# Cyusb3014_-_2.net
KiCad netlist of a schematic drawn in Altium Designer
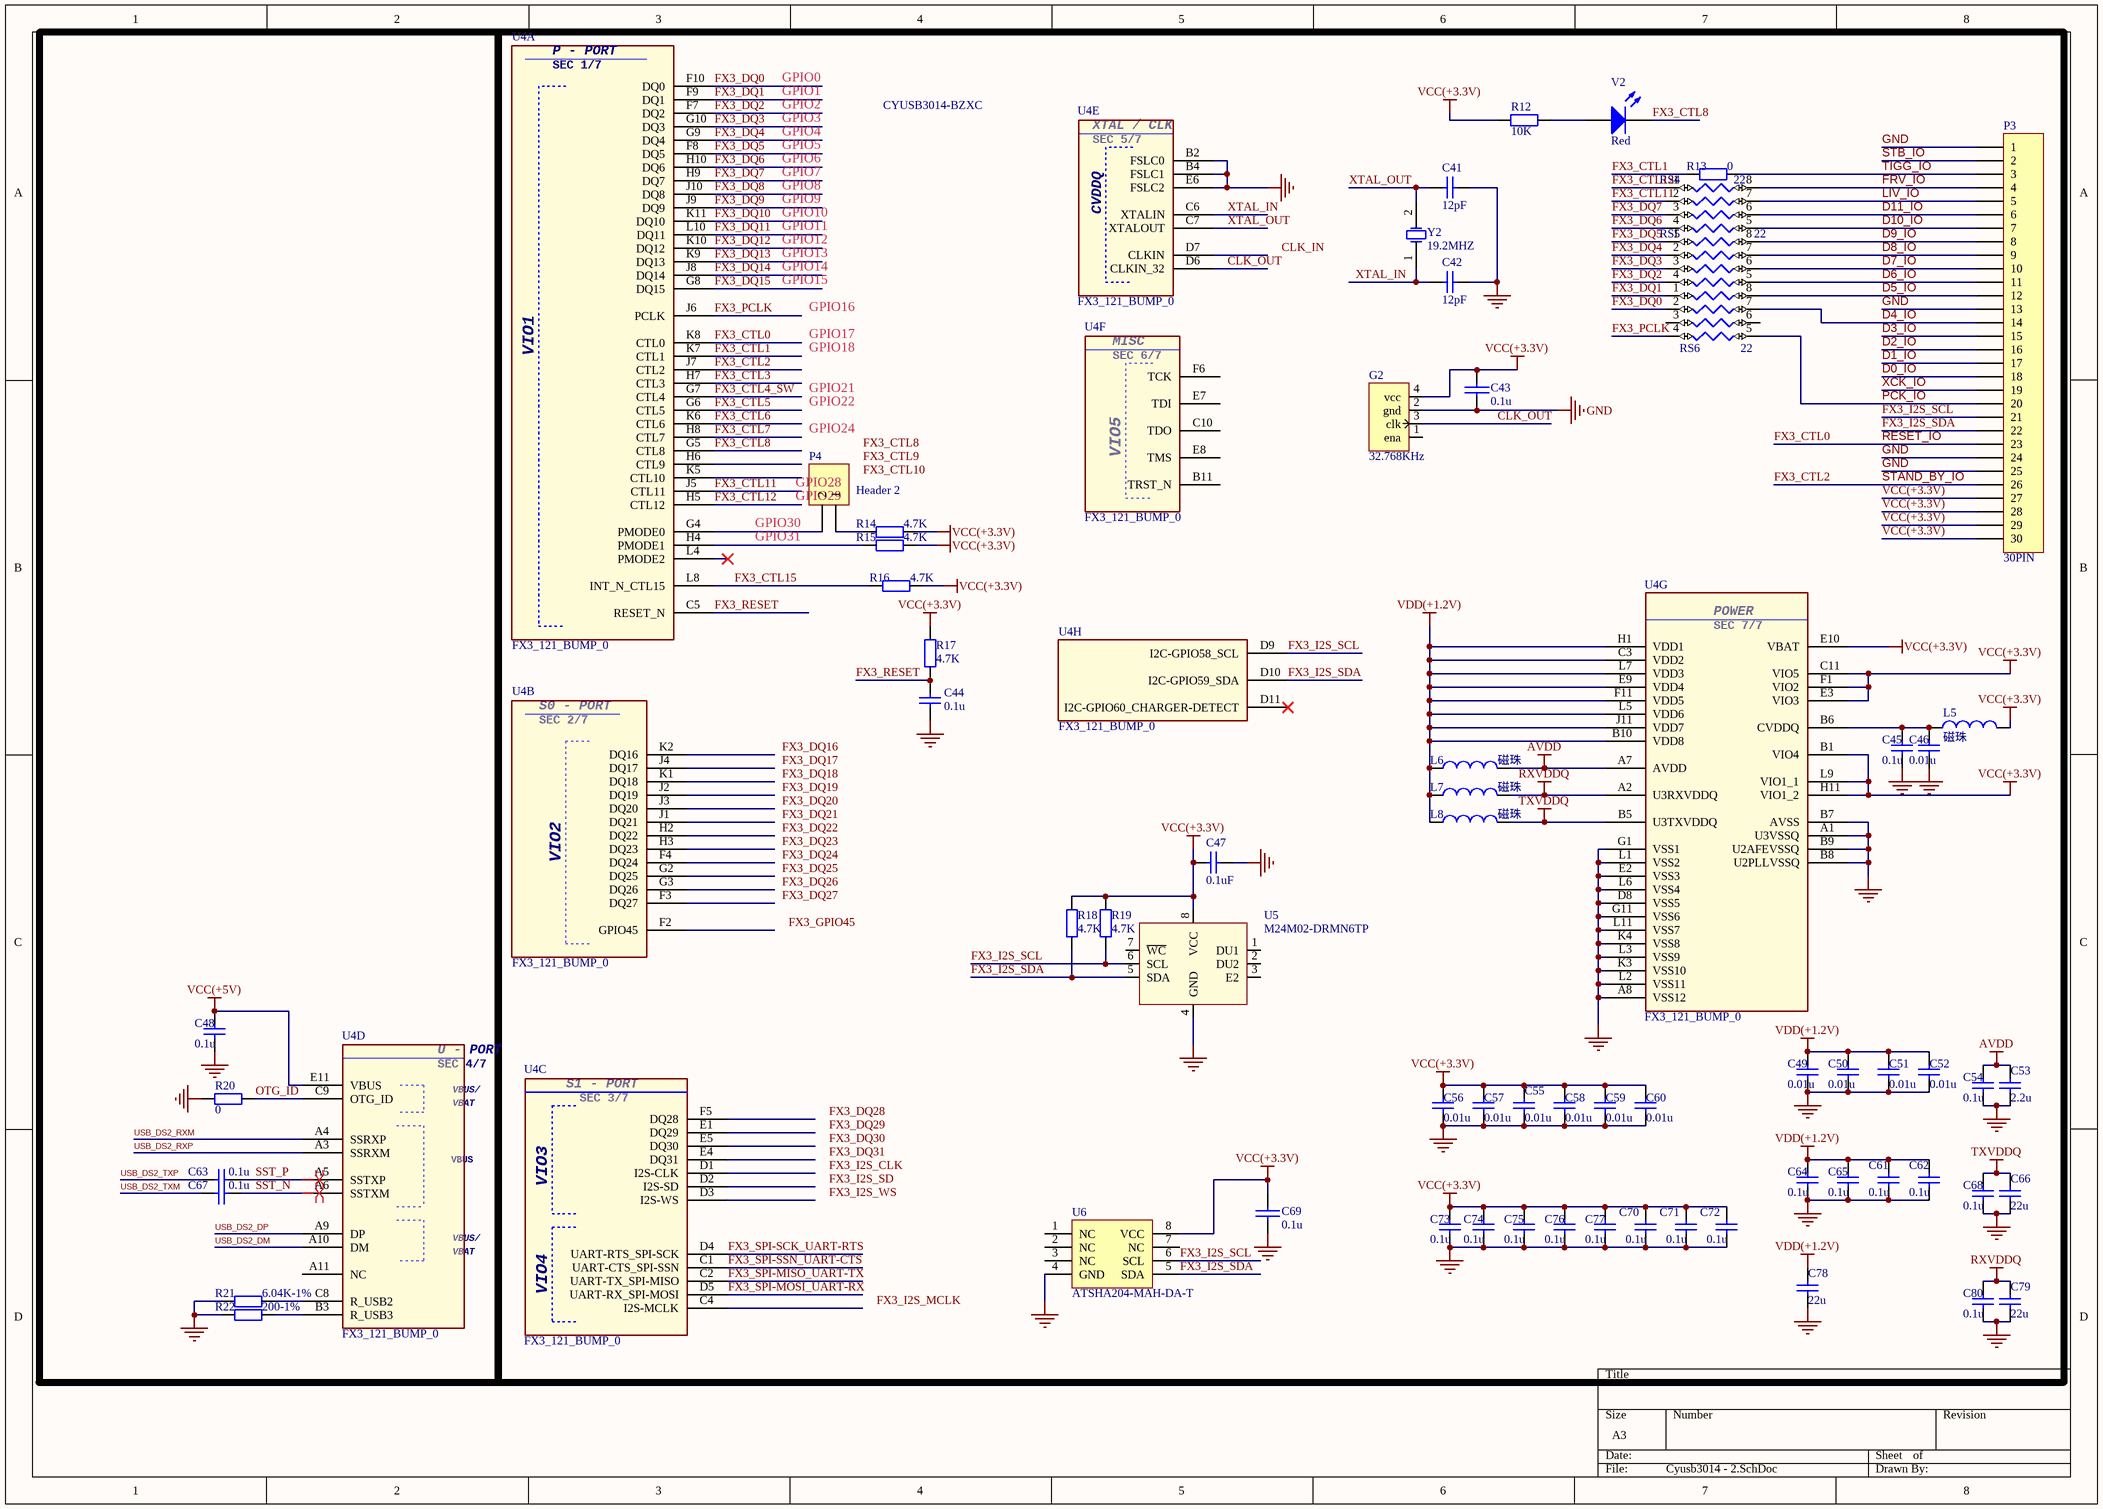
[diagram p0: Cyusb3014 - 2.SchDoc]

(export (version "E")
  (design (tool "Eeschema 10.0.6"))
  (components
    (comp (ref "C41")
      (value "12pF")
      (footprint "0603S-CAP")
      (description "CAP CER SMT 4.3pF 0805")
      (fields
        (field (name "2. MANUFACTURERE PART NUMBER") "C0805C439D5GACTU")
        (field (name "8. ALTERNATE PART") "any")
      )
      (libsource (lib "Peeple_eval") (part "CAP CER SMT 4.3pF 0805"))
    )
    (comp (ref "C42")
      (value "12pF")
      (footprint "0603S-CAP")
      (description "CAP CER SMT 4.3pF 0805")
      (fields
        (field (name "2. MANUFACTURERE PART NUMBER") "C0805C439D5GACTU")
        (field (name "8. ALTERNATE PART") "any")
      )
      (libsource (lib "Peeple_eval") (part "CAP CER SMT 4.3pF 0805"))
    )
    (comp (ref "C43")
      (value "0.1u")
      (footprint "0603S-CAP")
      (description "RC=1206")
      (libsource (lib "*") (part "CAP"))
    )
    (comp (ref "C44")
      (value "0.1u")
      (footprint "0603S-CAP")
      (description "50V/8.2u/0805")
      (fields (field (name "PUBLISHER") "Altium Limited"))
      (libsource (lib "Miscellaneous Devices") (part "Cap"))
    )
    (comp (ref "C45")
      (value "0.1u")
      (footprint "C0402")
      (description "Capacitor")
      (fields (field (name "PUBLISHER") "Altium Limited"))
      (libsource (lib "WM360") (part "CAP0805"))
    )
    (comp (ref "C46")
      (value "0.01u")
      (footprint "C0402")
      (description "Capacitor")
      (fields (field (name "PUBLISHER") "Altium Limited"))
      (libsource (lib "WM360") (part "CAP0805"))
    )
    (comp (ref "C47")
      (value "0.1uF")
      (footprint "0603S-CAP")
      (description "CAP SMT 0.1uF 16V X7R")
      (fields
        (field (name "2. MANUFACTURERE PART NUMBER") "C0805C104K4RACTU")
        (field (name "8. ALTERNATE PART") "any")
      )
      (libsource (lib "Peeple_eval") (part "CAP SMT 0.1uF 16V X7R"))
    )
    (comp (ref "C48")
      (value "0.1u")
      (footprint "C0402")
      (description "Capacitor")
      (fields (field (name "PUBLISHER") "Altium Limited"))
      (libsource (lib "WM360") (part "CAP0805"))
    )
    (comp (ref "C49")
      (value "0.01u")
      (footprint "C0402")
      (description "Capacitor")
      (fields (field (name "PUBLISHER") "Altium Limited"))
      (libsource (lib "WM360") (part "CAP0805"))
    )
    (comp (ref "C50")
      (value "0.01u")
      (footprint "C0402")
      (description "Capacitor")
      (fields (field (name "PUBLISHER") "Altium Limited"))
      (libsource (lib "WM360") (part "CAP0805"))
    )
    (comp (ref "C51")
      (value "0.01u")
      (footprint "C0402")
      (description "Capacitor")
      (fields (field (name "PUBLISHER") "Altium Limited"))
      (libsource (lib "WM360") (part "CAP0805"))
    )
    (comp (ref "C52")
      (value "0.01u")
      (footprint "C0402")
      (description "Capacitor")
      (fields (field (name "PUBLISHER") "Altium Limited"))
      (libsource (lib "WM360") (part "CAP0805"))
    )
    (comp (ref "C53")
      (value "2.2u")
      (footprint "C0805S-CAP")
      (description "Capacitor")
      (fields (field (name "PUBLISHER") "Altium Limited"))
      (libsource (lib "USB_CAMERA") (part "CAP0805"))
    )
    (comp (ref "C54")
      (value "0.1u")
      (footprint "C0402")
      (description "Capacitor")
      (fields (field (name "PUBLISHER") "Altium Limited"))
      (libsource (lib "WM360") (part "CAP0805"))
    )
    (comp (ref "C55")
      (value "0.01u")
      (footprint "C0402")
      (description "Capacitor")
      (fields (field (name "PUBLISHER") "Altium Limited"))
      (libsource (lib "WM360") (part "CAP0805"))
    )
    (comp (ref "C56")
      (value "0.01u")
      (footprint "C0402")
      (description "Capacitor")
      (fields (field (name "PUBLISHER") "Altium Limited"))
      (libsource (lib "WM360") (part "CAP0805"))
    )
    (comp (ref "C57")
      (value "0.01u")
      (footprint "C0402")
      (description "Capacitor")
      (fields (field (name "PUBLISHER") "Altium Limited"))
      (libsource (lib "WM360") (part "CAP0805"))
    )
    (comp (ref "C58")
      (value "0.01u")
      (footprint "C0402")
      (description "Capacitor")
      (fields (field (name "PUBLISHER") "Altium Limited"))
      (libsource (lib "WM360") (part "CAP0805"))
    )
    (comp (ref "C59")
      (value "0.01u")
      (footprint "C0402")
      (description "Capacitor")
      (fields (field (name "PUBLISHER") "Altium Limited"))
      (libsource (lib "WM360") (part "CAP0805"))
    )
    (comp (ref "C60")
      (value "0.01u")
      (footprint "C0402")
      (description "Capacitor")
      (fields (field (name "PUBLISHER") "Altium Limited"))
      (libsource (lib "WM360") (part "CAP0805"))
    )
    (comp (ref "C61")
      (value "0.1u")
      (footprint "C0402")
      (description "Capacitor")
      (fields (field (name "PUBLISHER") "Altium Limited"))
      (libsource (lib "WM360") (part "CAP0805"))
    )
    (comp (ref "C62")
      (value "0.1u")
      (footprint "C0402")
      (description "Capacitor")
      (fields (field (name "PUBLISHER") "Altium Limited"))
      (libsource (lib "WM360") (part "CAP0805"))
    )
    (comp (ref "C63")
      (value "0.1u")
      (footprint "C0402")
      (description "Capacitor")
      (fields (field (name "PUBLISHER") "Altium Limited"))
      (libsource (lib "WM360") (part "CAP0805"))
    )
    (comp (ref "C64")
      (value "0.1u")
      (footprint "C0402")
      (description "Capacitor")
      (fields (field (name "PUBLISHER") "Altium Limited"))
      (libsource (lib "WM360") (part "CAP0805"))
    )
    (comp (ref "C65")
      (value "0.1u")
      (footprint "C0402")
      (description "Capacitor")
      (fields (field (name "PUBLISHER") "Altium Limited"))
      (libsource (lib "WM360") (part "CAP0805"))
    )
    (comp (ref "C66")
      (value "22u")
      (footprint "C0805S-CAP")
      (description "Capacitor")
      (fields (field (name "PUBLISHER") "Altium Limited"))
      (libsource (lib "USB_CAMERA") (part "CAP0805"))
    )
    (comp (ref "C67")
      (value "0.1u")
      (footprint "C0402")
      (description "Capacitor")
      (fields (field (name "PUBLISHER") "Altium Limited"))
      (libsource (lib "WM360") (part "CAP0805"))
    )
    (comp (ref "C68")
      (value "0.1u")
      (footprint "C0402")
      (description "Capacitor")
      (fields (field (name "PUBLISHER") "Altium Limited"))
      (libsource (lib "WM360") (part "CAP0805"))
    )
    (comp (ref "C69")
      (value "0.1u")
      (footprint "0603S-CAP")
      (description "RC=1206")
      (libsource (lib "*") (part "CAP"))
    )
    (comp (ref "C70")
      (value "0.1u")
      (footprint "C0402")
      (description "Capacitor")
      (fields (field (name "PUBLISHER") "Altium Limited"))
      (libsource (lib "WM360") (part "CAP0805"))
    )
    (comp (ref "C71")
      (value "0.1u")
      (footprint "C0402")
      (description "Capacitor")
      (fields (field (name "PUBLISHER") "Altium Limited"))
      (libsource (lib "WM360") (part "CAP0805"))
    )
    (comp (ref "C72")
      (value "0.1u")
      (footprint "C0402")
      (description "Capacitor")
      (fields (field (name "PUBLISHER") "Altium Limited"))
      (libsource (lib "WM360") (part "CAP0805"))
    )
    (comp (ref "C73")
      (value "0.1u")
      (footprint "C0402")
      (description "Capacitor")
      (fields (field (name "PUBLISHER") "Altium Limited"))
      (libsource (lib "WM360") (part "CAP0805"))
    )
    (comp (ref "C74")
      (value "0.1u")
      (footprint "C0402")
      (description "Capacitor")
      (fields (field (name "PUBLISHER") "Altium Limited"))
      (libsource (lib "WM360") (part "CAP0805"))
    )
    (comp (ref "C75")
      (value "0.1u")
      (footprint "C0402")
      (description "Capacitor")
      (fields (field (name "PUBLISHER") "Altium Limited"))
      (libsource (lib "WM360") (part "CAP0805"))
    )
    (comp (ref "C76")
      (value "0.1u")
      (footprint "C0402")
      (description "Capacitor")
      (fields (field (name "PUBLISHER") "Altium Limited"))
      (libsource (lib "WM360") (part "CAP0805"))
    )
    (comp (ref "C77")
      (value "0.1u")
      (footprint "C0402")
      (description "Capacitor")
      (fields (field (name "PUBLISHER") "Altium Limited"))
      (libsource (lib "WM360") (part "CAP0805"))
    )
    (comp (ref "C78")
      (value "22u")
      (footprint "C0805S-CAP")
      (description "Capacitor")
      (fields (field (name "PUBLISHER") "Altium Limited"))
      (libsource (lib "USB_CAMERA") (part "CAP0805"))
    )
    (comp (ref "C79")
      (value "22u")
      (footprint "C0805S-CAP")
      (description "Capacitor")
      (fields (field (name "PUBLISHER") "Altium Limited"))
      (libsource (lib "USB_CAMERA") (part "CAP0805"))
    )
    (comp (ref "C80")
      (value "0.1u")
      (footprint "C0402")
      (description "Capacitor")
      (fields (field (name "PUBLISHER") "Altium Limited"))
      (libsource (lib "WM360") (part "CAP0805"))
    )
    (comp (ref "G2") (value "32.768KHz") (footprint "爱普生晶振3.2×2.5mm") (libsource (lib "*") (part "CTY4-B")))
    (comp (ref "L5")
      (value "磁珠")
      (footprint "L0603")
      (description "Inductor")
      (fields (field (name "PUBLISHER") "Altium Limited"))
      (libsource (lib "Miscellaneous Devices") (part "Inductor"))
    )
    (comp (ref "L6")
      (value "磁珠")
      (footprint "L0603")
      (description "Inductor")
      (fields (field (name "PUBLISHER") "Altium Limited"))
      (libsource (lib "Miscellaneous Devices") (part "Inductor"))
    )
    (comp (ref "L7")
      (value "磁珠")
      (footprint "L0603")
      (description "Inductor")
      (fields (field (name "PUBLISHER") "Altium Limited"))
      (libsource (lib "Miscellaneous Devices") (part "Inductor"))
    )
    (comp (ref "L8")
      (value "磁珠")
      (footprint "L0603")
      (description "Inductor")
      (fields (field (name "PUBLISHER") "Altium Limited"))
      (libsource (lib "Miscellaneous Devices") (part "Inductor"))
    )
    (comp (ref "P3")
      (value "30PIN")
      (footprint "FH12-30S-0.5SH")
      (description "Header, 30-Pin")
      (fields (field (name "PUBLISHER") "Altium Limited"))
      (libsource (lib "Miscellaneous Connectors") (part "Header 30"))
    )
    (comp (ref "P4")
      (value "Header 2")
      (footprint "HDR1X2")
      (description "Header, 2-Pin")
      (fields (field (name "PUBLISHER") "Altium Limited"))
      (libsource (lib "Miscellaneous Connectors") (part "Header 2"))
    )
    (comp (ref "R12")
      (value "10K")
      (footprint "0603S-RES")
      (description "Resistor")
      (fields (field (name "PUBLISHER") "Altium Limited"))
      (libsource (lib "") (part "Res2_1"))
    )
    (comp (ref "R13")
      (value "0")
      (footprint "0603S-RES")
      (description "Resistor")
      (fields (field (name "PUBLISHER") "Altium Limited"))
      (libsource (lib "") (part "Res2_1"))
    )
    (comp (ref "R14")
      (value "4.7K")
      (footprint "0603S-RES")
      (description "Resistor")
      (fields (field (name "PUBLISHER") "Altium Limited"))
      (libsource (lib "") (part "Res2_2"))
    )
    (comp (ref "R15")
      (value "4.7K")
      (footprint "0603S-RES")
      (description "Resistor")
      (fields (field (name "PUBLISHER") "Altium Limited"))
      (libsource (lib "") (part "Res2_2"))
    )
    (comp (ref "R16")
      (value "4.7K")
      (footprint "0603S-RES")
      (description "Resistor")
      (fields (field (name "PUBLISHER") "Altium Limited"))
      (libsource (lib "DM642") (part "Res2"))
    )
    (comp (ref "R17")
      (value "4.7K")
      (footprint "0603S-RES")
      (description "Resistor")
      (fields (field (name "PUBLISHER") "Altium Limited"))
      (libsource (lib "") (part "Res2_3"))
    )
    (comp (ref "R18")
      (value "4.7K")
      (footprint "0603S-RES")
      (description "Resistor")
      (fields (field (name "PUBLISHER") "Altium Limited"))
      (libsource (lib "") (part "Res2_2"))
    )
    (comp (ref "R19")
      (value "4.7K")
      (footprint "0603S-RES")
      (description "Resistor")
      (fields (field (name "PUBLISHER") "Altium Limited"))
      (libsource (lib "") (part "Res2_2"))
    )
    (comp (ref "R20")
      (value "0")
      (footprint "0603S-RES")
      (description "Resistor")
      (fields (field (name "PUBLISHER") "Altium Limited"))
      (libsource (lib "DM642") (part "Res2"))
    )
    (comp (ref "R21")
      (value "6.04K-1%")
      (footprint "0603S-RES")
      (description "Resistor")
      (fields (field (name "PUBLISHER") "Altium Limited"))
      (libsource (lib "DM642") (part "Res2"))
    )
    (comp (ref "R22")
      (value "200-1%")
      (footprint "0603S-RES")
      (description "Resistor")
      (fields (field (name "PUBLISHER") "Altium Limited"))
      (libsource (lib "DM642") (part "Res2"))
    )
    (comp (ref "RS4") (value "22") (footprint "NC06-4") (libsource (lib "*") (part "RN4")))
    (comp (ref "RS5") (value "22") (footprint "NC06-4") (libsource (lib "*") (part "RN4")))
    (comp (ref "RS6") (value "22") (footprint "NC06-4") (libsource (lib "*") (part "RN4")))
    (comp (ref "U4")
      (value "FX3_121_BUMP_0")
      (footprint "121_BGA_FX3")
      (libsource (lib "USB_CAMERA") (part "FX3_121_BUMP_0"))
    )
    (comp (ref "U5")
      (value "M24M02-DRMN6TP")
      (footprint "SOIC127P600X175-8N")
      (description "IC EEPROM 64KBIT 400KHZ 8SOIC")
      (fields
        (field (name "MANUFACTURER") "Microchip Technology")
        (field (name "MANUFACTURER PART NUMBER") "24LC64-I/SN")
      )
      (libsource (lib "Schlib1") (part "24LC64-I/SN"))
    )
    (comp (ref "U6")
      (value "ATSHA204-MAH-DA-T")
      (footprint "UDFN")
      (libsource (lib "CY7C68013-56") (part "AT24C128"))
    )
    (comp (ref "V2")
      (value "Red")
      (footprint "LED0805S")
      (description "Typical INFRARED GaAs LED")
      (fields (field (name "PUBLISHER") "Altium Limited"))
      (libsource (lib "DM642") (part "LED0"))
    )
    (comp (ref "Y2")
      (value "19.2MHZ")
      (footprint "爱普生晶振3.2×2.5MM - 无源")
      (description "Crystal, CRYSTAL 32.768KHZ 6PF SMD")
      (fields
        (field (name "2. MANUFACTURERE PART NUMBER") "ABS07-120-32.768KHZ-T")
        (field (name "4. SUPPLIER PART NUMBER") "535-11937-1-ND")
      )
      (libsource (lib "Peeple_eval") (part "XTAL 32.768KHZ"))
    )
  )
  (nets
    (net (code "2") (name "/CLK_OUT") (class "Default")
      (node (ref "G2") (pin "3") (pinfunction "clk_3") (pintype "passive"))
      (node (ref "U4") (pin "D6") (pinfunction "CLKIN_32_D6") (pintype "passive"))
    )
    (net (code "3") (name "/D0_IO") (class "Default")
      (node (ref "P3") (pin "18") (pinfunction "18_18") (pintype "passive"))
    )
    (net (code "4") (name "/D1_IO") (class "Default")
      (node (ref "P3") (pin "17") (pinfunction "17_17") (pintype "passive"))
    )
    (net (code "5") (name "/D2_IO") (class "Default")
      (node (ref "P3") (pin "16") (pinfunction "16_16") (pintype "passive"))
    )
    (net (code "6") (name "/D3_IO") (class "Default")
      (node (ref "P3") (pin "15") (pinfunction "15_15") (pintype "passive"))
    )
    (net (code "7") (name "/D4_IO") (class "Default")
      (node (ref "P3") (pin "14") (pinfunction "14_14") (pintype "passive"))
      (node (ref "RS6") (pin "7") (pinfunction "7_7") (pintype "bidirectional"))
    )
    (net (code "8") (name "/D5_IO") (class "Default")
      (node (ref "P3") (pin "12") (pinfunction "12_12") (pintype "passive"))
      (node (ref "RS6") (pin "8") (pinfunction "8_8") (pintype "bidirectional"))
    )
    (net (code "9") (name "/D6_IO") (class "Default")
      (node (ref "P3") (pin "11") (pinfunction "11_11") (pintype "passive"))
      (node (ref "RS5") (pin "5") (pinfunction "5_5") (pintype "bidirectional"))
    )
    (net (code "10") (name "/D7_IO") (class "Default")
      (node (ref "P3") (pin "10") (pinfunction "10_10") (pintype "passive"))
      (node (ref "RS5") (pin "6") (pinfunction "6_6") (pintype "bidirectional"))
    )
    (net (code "11") (name "/D8_IO") (class "Default")
      (node (ref "P3") (pin "9") (pinfunction "9_9") (pintype "passive"))
      (node (ref "RS5") (pin "7") (pinfunction "7_7") (pintype "bidirectional"))
    )
    (net (code "12") (name "/D9_IO") (class "Default")
      (node (ref "P3") (pin "8") (pinfunction "8_8") (pintype "passive"))
      (node (ref "RS5") (pin "8") (pinfunction "8_8") (pintype "bidirectional"))
    )
    (net (code "13") (name "/D10_IO") (class "Default")
      (node (ref "P3") (pin "7") (pinfunction "7_7") (pintype "passive"))
      (node (ref "RS4") (pin "5") (pinfunction "5_5") (pintype "bidirectional"))
    )
    (net (code "14") (name "/D11_IO") (class "Default")
      (node (ref "P3") (pin "6") (pinfunction "6_6") (pintype "passive"))
      (node (ref "RS4") (pin "6") (pinfunction "6_6") (pintype "bidirectional"))
    )
    (net (code "15") (name "/FRV_IO") (class "Default")
      (node (ref "P3") (pin "4") (pinfunction "4_4") (pintype "passive"))
      (node (ref "RS4") (pin "8") (pinfunction "8_8") (pintype "bidirectional"))
    )
    (net (code "16") (name "/FX3_CTL0") (class "Default")
      (node (ref "P3") (pin "23") (pinfunction "23_23") (pintype "passive"))
      (node (ref "U4") (pin "K8") (pinfunction "CTL0_K8") (pintype "passive"))
    )
    (net (code "17") (name "/FX3_CTL1") (class "Default")
      (node (ref "R13") (pin "2") (pinfunction "2_2") (pintype "passive"))
      (node (ref "U4") (pin "K7") (pinfunction "CTL1_K7") (pintype "passive"))
    )
    (net (code "18") (name "/FX3_CTL2") (class "Default")
      (node (ref "P3") (pin "26") (pinfunction "26_26") (pintype "passive"))
      (node (ref "U4") (pin "J7") (pinfunction "CTL2_J7") (pintype "passive"))
    )
    (net (code "19") (name "/FX3_CTL3") (class "Default")
      (node (ref "U4") (pin "H7") (pinfunction "CTL3_H7") (pintype "passive"))
    )
    (net (code "20") (name "/FX3_CTL4_SW") (class "Default")
      (node (ref "U4") (pin "G7") (pinfunction "CTL4_G7") (pintype "passive"))
    )
    (net (code "21") (name "/FX3_CTL5") (class "Default")
      (node (ref "U4") (pin "G6") (pinfunction "CTL5_G6") (pintype "passive"))
    )
    (net (code "22") (name "/FX3_CTL6") (class "Default")
      (node (ref "U4") (pin "K6") (pinfunction "CTL6_K6") (pintype "passive"))
    )
    (net (code "23") (name "/FX3_CTL7") (class "Default")
      (node (ref "U4") (pin "H8") (pinfunction "CTL7_H8") (pintype "passive"))
    )
    (net (code "24") (name "/FX3_CTL8") (class "Default")
      (node (ref "U4") (pin "G5") (pinfunction "CTL8_G5") (pintype "passive"))
      (node (ref "V2") (pin "2") (pinfunction "K_2") (pintype "passive"))
    )
    (net (code "27") (name "/FX3_CTL11") (class "Default")
      (node (ref "RS4") (pin "2") (pinfunction "2_2") (pintype "bidirectional"))
      (node (ref "U4") (pin "J5") (pinfunction "CTL11_J5") (pintype "passive"))
    )
    (net (code "28") (name "/FX3_CTL12") (class "Default")
      (node (ref "RS4") (pin "1") (pinfunction "1_1") (pintype "bidirectional"))
      (node (ref "U4") (pin "H5") (pinfunction "CTL12_H5") (pintype "passive"))
    )
    (net (code "29") (name "/FX3_CTL15") (class "Default")
      (node (ref "R16") (pin "2") (pinfunction "2_2") (pintype "passive"))
      (node (ref "U4") (pin "L8") (pinfunction "INT_N_CTL15_L8") (pintype "passive"))
    )
    (net (code "30") (name "/FX3_DQ0") (class "Default")
      (node (ref "RS6") (pin "2") (pinfunction "2_2") (pintype "bidirectional"))
      (node (ref "U4") (pin "F10") (pinfunction "DQ0_F10") (pintype "passive"))
    )
    (net (code "31") (name "/FX3_DQ1") (class "Default")
      (node (ref "RS6") (pin "1") (pinfunction "1_1") (pintype "bidirectional"))
      (node (ref "U4") (pin "F9") (pinfunction "DQ1_F9") (pintype "passive"))
    )
    (net (code "32") (name "/FX3_DQ2") (class "Default")
      (node (ref "RS5") (pin "4") (pinfunction "4_4") (pintype "bidirectional"))
      (node (ref "U4") (pin "F7") (pinfunction "DQ2_F7") (pintype "passive"))
    )
    (net (code "33") (name "/FX3_DQ3") (class "Default")
      (node (ref "RS5") (pin "3") (pinfunction "3_3") (pintype "bidirectional"))
      (node (ref "U4") (pin "G10") (pinfunction "DQ3_G10") (pintype "passive"))
    )
    (net (code "34") (name "/FX3_DQ4") (class "Default")
      (node (ref "RS5") (pin "2") (pinfunction "2_2") (pintype "bidirectional"))
      (node (ref "U4") (pin "G9") (pinfunction "DQ4_G9") (pintype "passive"))
    )
    (net (code "35") (name "/FX3_DQ5") (class "Default")
      (node (ref "RS5") (pin "1") (pinfunction "1_1") (pintype "bidirectional"))
      (node (ref "U4") (pin "F8") (pinfunction "DQ5_F8") (pintype "passive"))
    )
    (net (code "36") (name "/FX3_DQ6") (class "Default")
      (node (ref "RS4") (pin "4") (pinfunction "4_4") (pintype "bidirectional"))
      (node (ref "U4") (pin "H10") (pinfunction "DQ6_H10") (pintype "passive"))
    )
    (net (code "37") (name "/FX3_DQ7") (class "Default")
      (node (ref "RS4") (pin "3") (pinfunction "3_3") (pintype "bidirectional"))
      (node (ref "U4") (pin "H9") (pinfunction "DQ7_H9") (pintype "passive"))
    )
    (net (code "38") (name "/FX3_DQ8") (class "Default")
      (node (ref "U4") (pin "J10") (pinfunction "DQ8_J10") (pintype "passive"))
    )
    (net (code "39") (name "/FX3_DQ9") (class "Default")
      (node (ref "U4") (pin "J9") (pinfunction "DQ9_J9") (pintype "passive"))
    )
    (net (code "40") (name "/FX3_DQ10") (class "Default")
      (node (ref "U4") (pin "K11") (pinfunction "DQ10_K11") (pintype "passive"))
    )
    (net (code "41") (name "/FX3_DQ11") (class "Default")
      (node (ref "U4") (pin "L10") (pinfunction "DQ11_L10") (pintype "passive"))
    )
    (net (code "42") (name "/FX3_DQ12") (class "Default")
      (node (ref "U4") (pin "K10") (pinfunction "DQ12_K10") (pintype "passive"))
    )
    (net (code "43") (name "/FX3_DQ13") (class "Default")
      (node (ref "U4") (pin "K9") (pinfunction "DQ13_K9") (pintype "passive"))
    )
    (net (code "44") (name "/FX3_DQ14") (class "Default")
      (node (ref "U4") (pin "J8") (pinfunction "DQ14_J8") (pintype "passive"))
    )
    (net (code "45") (name "/FX3_DQ15") (class "Default")
      (node (ref "U4") (pin "G8") (pinfunction "DQ15_G8") (pintype "passive"))
    )
    (net (code "65") (name "/FX3_I2S_SCL") (class "Default")
      (node (ref "P3") (pin "21") (pinfunction "21_21") (pintype "passive"))
      (node (ref "R19") (pin "1") (pinfunction "1_1") (pintype "passive"))
      (node (ref "U4") (pin "D9") (pinfunction "I2C-GPIO58_SCL_D9") (pintype "passive"))
      (node (ref "U5") (pin "6") (pinfunction "SCL_6") (pintype "passive"))
      (node (ref "U6") (pin "6") (pinfunction "SCL_6") (pintype "passive"))
    )
    (net (code "67") (name "/FX3_I2S_SDA") (class "Default")
      (node (ref "P3") (pin "22") (pinfunction "22_22") (pintype "passive"))
      (node (ref "R18") (pin "1") (pinfunction "1_1") (pintype "passive"))
      (node (ref "U4") (pin "D10") (pinfunction "I2C-GPIO59_SDA_D10") (pintype "passive"))
      (node (ref "U5") (pin "5") (pinfunction "SDA_5") (pintype "passive"))
      (node (ref "U6") (pin "5") (pinfunction "SDA_5") (pintype "passive"))
    )
    (net (code "69") (name "/FX3_PCLK") (class "Default")
      (node (ref "RS6") (pin "4") (pinfunction "4_4") (pintype "bidirectional"))
      (node (ref "U4") (pin "J6") (pinfunction "PCLK_J6") (pintype "passive"))
    )
    (net (code "70") (name "/FX3_RESET") (class "Default")
      (node (ref "C44") (pin "2") (pinfunction "2_2") (pintype "passive"))
      (node (ref "R17") (pin "2") (pinfunction "2_2") (pintype "passive"))
      (node (ref "U4") (pin "C5") (pinfunction "RESET_N_C5") (pintype "passive"))
    )
    (net (code "71") (name "/FX3_SPI-MISO_UART-TX") (class "Default")
      (node (ref "U4") (pin "C2") (pinfunction "UART-TX_SPI-MISO_C2") (pintype "passive"))
    )
    (net (code "72") (name "/FX3_SPI-MOSI_UART-RX") (class "Default")
      (node (ref "U4") (pin "D5") (pinfunction "UART-RX_SPI-MOSI_D5") (pintype "passive"))
    )
    (net (code "73") (name "/FX3_SPI-SCK_UART-RTS") (class "Default")
      (node (ref "U4") (pin "D4") (pinfunction "UART-RTS_SPI-SCK_D4") (pintype "passive"))
    )
    (net (code "74") (name "/FX3_SPI-SSN_UART-CTS") (class "Default")
      (node (ref "U4") (pin "C1") (pinfunction "UART-CTS_SPI-SSN_C1") (pintype "passive"))
    )
    (net (code "75") (name "/LIV_IO") (class "Default")
      (node (ref "P3") (pin "5") (pinfunction "5_5") (pintype "passive"))
      (node (ref "RS4") (pin "7") (pinfunction "7_7") (pintype "bidirectional"))
    )
    (net (code "76") (name "/OTG_ID") (class "Default")
      (node (ref "R20") (pin "1") (pinfunction "1_1") (pintype "passive"))
      (node (ref "U4") (pin "C9") (pinfunction "OTG_ID_C9") (pintype "passive"))
    )
    (net (code "77") (name "/PCK_IO") (class "Default")
      (node (ref "P3") (pin "20") (pinfunction "20_20") (pintype "passive"))
      (node (ref "RS6") (pin "5") (pinfunction "5_5") (pintype "bidirectional"))
    )
    (net (code "78") (name "/SST_N") (class "Default")
      (node (ref "C67") (pin "2") (pinfunction "2_2") (pintype "passive"))
      (node (ref "U4") (pin "A6") (pinfunction "SSTXM_A6") (pintype "passive"))
    )
    (net (code "79") (name "/SST_P") (class "Default")
      (node (ref "C63") (pin "2") (pinfunction "2_2") (pintype "passive"))
      (node (ref "U4") (pin "A5") (pinfunction "SSTXP_A5") (pintype "passive"))
    )
    (net (code "80") (name "/STB_IO") (class "Default")
      (node (ref "P3") (pin "2") (pinfunction "2_2") (pintype "passive"))
    )
    (net (code "81") (name "/TIGG_IO") (class "Default")
      (node (ref "P3") (pin "3") (pinfunction "3_3") (pintype "passive"))
      (node (ref "R13") (pin "1") (pinfunction "1_1") (pintype "passive"))
    )
    (net (code "82") (name "/USB_DS2_DM") (class "Default")
      (node (ref "U4") (pin "A10") (pinfunction "DM_A10") (pintype "passive"))
    )
    (net (code "83") (name "/USB_DS2_DP") (class "Default")
      (node (ref "U4") (pin "A9") (pinfunction "DP_A9") (pintype "passive"))
    )
    (net (code "84") (name "/USB_DS2_RXM") (class "Default")
      (node (ref "U4") (pin "A4") (pinfunction "SSRXP_A4") (pintype "passive"))
    )
    (net (code "85") (name "/USB_DS2_RXP") (class "Default")
      (node (ref "U4") (pin "A3") (pinfunction "SSRXM_A3") (pintype "passive"))
    )
    (net (code "86") (name "/USB_DS2_TXM") (class "Default")
      (node (ref "C67") (pin "1") (pinfunction "1_1") (pintype "passive"))
    )
    (net (code "87") (name "/USB_DS2_TXP") (class "Default")
      (node (ref "C63") (pin "1") (pinfunction "1_1") (pintype "passive"))
    )
    (net (code "88") (name "/XCK_IO") (class "Default")
      (node (ref "P3") (pin "19") (pinfunction "19_19") (pintype "passive"))
    )
    (net (code "89") (name "/XTAL_IN") (class "Default")
      (node (ref "C42") (pin "2") (pinfunction "2_2") (pintype "passive"))
      (node (ref "U4") (pin "C6") (pinfunction "XTALIN_C6") (pintype "passive"))
      (node (ref "Y2") (pin "1") (pinfunction "OSC1_1") (pintype "passive"))
    )
    (net (code "90") (name "/XTAL_OUT") (class "Default")
      (node (ref "C41") (pin "2") (pinfunction "2_2") (pintype "passive"))
      (node (ref "U4") (pin "C7") (pinfunction "XTALOUT_C7") (pintype "passive"))
      (node (ref "Y2") (pin "2") (pinfunction "OSC2_2") (pintype "passive"))
    )
    (net (code "91") (name "AVDD") (class "Default")
      (node (ref "C53") (pin "2") (pinfunction "2_2") (pintype "passive"))
      (node (ref "C54") (pin "1") (pinfunction "1_1") (pintype "passive"))
      (node (ref "L6") (pin "2") (pinfunction "2_2") (pintype "passive"))
      (node (ref "U4") (pin "A7") (pinfunction "AVDD_A7") (pintype "passive"))
    )
    (net (code "92") (name "GND") (class "Default")
      (node (ref "C41") (pin "1") (pinfunction "1_1") (pintype "passive"))
      (node (ref "C42") (pin "1") (pinfunction "1_1") (pintype "passive"))
      (node (ref "C43") (pin "2") (pintype "passive"))
      (node (ref "C44") (pin "1") (pinfunction "1_1") (pintype "passive"))
      (node (ref "C45") (pin "2") (pinfunction "2_2") (pintype "passive"))
      (node (ref "C46") (pin "2") (pinfunction "2_2") (pintype "passive"))
      (node (ref "C47") (pin "1") (pinfunction "1_1") (pintype "passive"))
      (node (ref "C48") (pin "2") (pinfunction "2_2") (pintype "passive"))
      (node (ref "C49") (pin "2") (pinfunction "2_2") (pintype "passive"))
      (node (ref "C50") (pin "2") (pinfunction "2_2") (pintype "passive"))
      (node (ref "C51") (pin "2") (pinfunction "2_2") (pintype "passive"))
      (node (ref "C52") (pin "2") (pinfunction "2_2") (pintype "passive"))
      (node (ref "C53") (pin "1") (pinfunction "1_1") (pintype "passive"))
      (node (ref "C54") (pin "2") (pinfunction "2_2") (pintype "passive"))
      (node (ref "C55") (pin "2") (pinfunction "2_2") (pintype "passive"))
      (node (ref "C56") (pin "2") (pinfunction "2_2") (pintype "passive"))
      (node (ref "C57") (pin "2") (pinfunction "2_2") (pintype "passive"))
      (node (ref "C58") (pin "2") (pinfunction "2_2") (pintype "passive"))
      (node (ref "C59") (pin "2") (pinfunction "2_2") (pintype "passive"))
      (node (ref "C60") (pin "2") (pinfunction "2_2") (pintype "passive"))
      (node (ref "C61") (pin "2") (pinfunction "2_2") (pintype "passive"))
      (node (ref "C62") (pin "2") (pinfunction "2_2") (pintype "passive"))
      (node (ref "C64") (pin "2") (pinfunction "2_2") (pintype "passive"))
      (node (ref "C65") (pin "2") (pinfunction "2_2") (pintype "passive"))
      (node (ref "C66") (pin "1") (pinfunction "1_1") (pintype "passive"))
      (node (ref "C68") (pin "2") (pinfunction "2_2") (pintype "passive"))
      (node (ref "C69") (pin "2") (pintype "passive"))
      (node (ref "C70") (pin "2") (pinfunction "2_2") (pintype "passive"))
      (node (ref "C71") (pin "2") (pinfunction "2_2") (pintype "passive"))
      (node (ref "C72") (pin "2") (pinfunction "2_2") (pintype "passive"))
      (node (ref "C73") (pin "2") (pinfunction "2_2") (pintype "passive"))
      (node (ref "C74") (pin "2") (pinfunction "2_2") (pintype "passive"))
      (node (ref "C75") (pin "2") (pinfunction "2_2") (pintype "passive"))
      (node (ref "C76") (pin "2") (pinfunction "2_2") (pintype "passive"))
      (node (ref "C77") (pin "2") (pinfunction "2_2") (pintype "passive"))
      (node (ref "C78") (pin "1") (pinfunction "1_1") (pintype "passive"))
      (node (ref "C79") (pin "1") (pinfunction "1_1") (pintype "passive"))
      (node (ref "C80") (pin "2") (pinfunction "2_2") (pintype "passive"))
      (node (ref "G2") (pin "2") (pinfunction "gnd_2") (pintype "power_in"))
      (node (ref "P3") (pin "1") (pinfunction "1_1") (pintype "passive"))
      (node (ref "P3") (pin "13") (pinfunction "13_13") (pintype "passive"))
      (node (ref "P3") (pin "24") (pinfunction "24_24") (pintype "passive"))
      (node (ref "P3") (pin "25") (pinfunction "25_25") (pintype "passive"))
      (node (ref "R20") (pin "2") (pinfunction "2_2") (pintype "passive"))
      (node (ref "R21") (pin "2") (pinfunction "2_2") (pintype "passive"))
      (node (ref "R22") (pin "2") (pinfunction "2_2") (pintype "passive"))
      (node (ref "U4") (pin "A1") (pinfunction "U3VSSQ_A1") (pintype "passive"))
      (node (ref "U4") (pin "A8") (pinfunction "VSS12_A8") (pintype "passive"))
      (node (ref "U4") (pin "B2") (pinfunction "FSLC0_B2") (pintype "passive"))
      (node (ref "U4") (pin "B4") (pinfunction "FSLC1_B4") (pintype "passive"))
      (node (ref "U4") (pin "B7") (pinfunction "AVSS_B7") (pintype "passive"))
      (node (ref "U4") (pin "B8") (pinfunction "U2PLLVSSQ_B8") (pintype "passive"))
      (node (ref "U4") (pin "B9") (pinfunction "U2AFEVSSQ_B9") (pintype "passive"))
      (node (ref "U4") (pin "D8") (pinfunction "VSS5_D8") (pintype "passive"))
      (node (ref "U4") (pin "E2") (pinfunction "VSS3_E2") (pintype "passive"))
      (node (ref "U4") (pin "E6") (pinfunction "FSLC2_E6") (pintype "passive"))
      (node (ref "U4") (pin "G1") (pinfunction "VSS1_G1") (pintype "passive"))
      (node (ref "U4") (pin "G11") (pinfunction "VSS6_G11") (pintype "passive"))
      (node (ref "U4") (pin "K3") (pinfunction "VSS10_K3") (pintype "passive"))
      (node (ref "U4") (pin "K4") (pinfunction "VSS8_K4") (pintype "passive"))
      (node (ref "U4") (pin "L1") (pinfunction "VSS2_L1") (pintype "passive"))
      (node (ref "U4") (pin "L11") (pinfunction "VSS7_L11") (pintype "passive"))
      (node (ref "U4") (pin "L2") (pinfunction "VSS11_L2") (pintype "passive"))
      (node (ref "U4") (pin "L3") (pinfunction "VSS9_L3") (pintype "passive"))
      (node (ref "U4") (pin "L6") (pinfunction "VSS4_L6") (pintype "passive"))
      (node (ref "U5") (pin "4") (pinfunction "GND_4") (pintype "passive"))
      (node (ref "U6") (pin "4") (pinfunction "GND_4") (pintype "passive"))
    )
    (net (code "93") (name "Net-(P4-Pad1)") (class "Default")
      (node (ref "P4") (pin "1") (pinfunction "1_1") (pintype "passive"))
      (node (ref "R14") (pin "1") (pinfunction "1_1") (pintype "passive"))
    )
    (net (code "94") (name "Net-(U4A-PMODE0)") (class "Default")
      (node (ref "P4") (pin "2") (pinfunction "2_2") (pintype "passive"))
      (node (ref "U4") (pin "G4") (pinfunction "PMODE0_G4") (pintype "passive"))
    )
    (net (code "95") (name "Net-(U4A-PMODE1)") (class "Default")
      (node (ref "R15") (pin "1") (pinfunction "1_1") (pintype "passive"))
      (node (ref "U4") (pin "H4") (pinfunction "PMODE1_H4") (pintype "passive"))
    )
    (net (code "96") (name "Net-(U4D-R_USB2)") (class "Default")
      (node (ref "R21") (pin "1") (pinfunction "1_1") (pintype "passive"))
      (node (ref "U4") (pin "C8") (pinfunction "R_USB2_C8") (pintype "passive"))
    )
    (net (code "97") (name "Net-(U4D-R_USB3)") (class "Default")
      (node (ref "R22") (pin "1") (pinfunction "1_1") (pintype "passive"))
      (node (ref "U4") (pin "B3") (pinfunction "R_USB3_B3") (pintype "passive"))
    )
    (net (code "98") (name "Net-(U4G-CVDDQ)") (class "Default")
      (node (ref "C45") (pin "1") (pinfunction "1_1") (pintype "passive"))
      (node (ref "C46") (pin "1") (pinfunction "1_1") (pintype "passive"))
      (node (ref "L5") (pin "1") (pinfunction "1_1") (pintype "passive"))
      (node (ref "U4") (pin "B6") (pinfunction "CVDDQ_B6") (pintype "passive"))
    )
    (net (code "99") (name "Net-(V2-A)") (class "Default")
      (node (ref "R12") (pin "1") (pinfunction "1_1") (pintype "passive"))
      (node (ref "V2") (pin "1") (pinfunction "A_1") (pintype "passive"))
    )
    (net (code "100") (name "RXVDDQ") (class "Default")
      (node (ref "C79") (pin "2") (pinfunction "2_2") (pintype "passive"))
      (node (ref "C80") (pin "1") (pinfunction "1_1") (pintype "passive"))
      (node (ref "L7") (pin "2") (pinfunction "2_2") (pintype "passive"))
      (node (ref "U4") (pin "A2") (pinfunction "U3RXVDDQ_A2") (pintype "passive"))
    )
    (net (code "101") (name "TXVDDQ") (class "Default")
      (node (ref "C66") (pin "2") (pinfunction "2_2") (pintype "passive"))
      (node (ref "C68") (pin "1") (pinfunction "1_1") (pintype "passive"))
      (node (ref "L8") (pin "2") (pinfunction "2_2") (pintype "passive"))
      (node (ref "U4") (pin "B5") (pinfunction "U3TXVDDQ_B5") (pintype "passive"))
    )
    (net (code "102") (name "VCC(+3.3V)") (class "Default")
      (node (ref "C43") (pin "1") (pintype "passive"))
      (node (ref "C47") (pin "2") (pinfunction "2_2") (pintype "passive"))
      (node (ref "C55") (pin "1") (pinfunction "1_1") (pintype "passive"))
      (node (ref "C56") (pin "1") (pinfunction "1_1") (pintype "passive"))
      (node (ref "C57") (pin "1") (pinfunction "1_1") (pintype "passive"))
      (node (ref "C58") (pin "1") (pinfunction "1_1") (pintype "passive"))
      (node (ref "C59") (pin "1") (pinfunction "1_1") (pintype "passive"))
      (node (ref "C60") (pin "1") (pinfunction "1_1") (pintype "passive"))
      (node (ref "C69") (pin "1") (pintype "passive"))
      (node (ref "C70") (pin "1") (pinfunction "1_1") (pintype "passive"))
      (node (ref "C71") (pin "1") (pinfunction "1_1") (pintype "passive"))
      (node (ref "C72") (pin "1") (pinfunction "1_1") (pintype "passive"))
      (node (ref "C73") (pin "1") (pinfunction "1_1") (pintype "passive"))
      (node (ref "C74") (pin "1") (pinfunction "1_1") (pintype "passive"))
      (node (ref "C75") (pin "1") (pinfunction "1_1") (pintype "passive"))
      (node (ref "C76") (pin "1") (pinfunction "1_1") (pintype "passive"))
      (node (ref "C77") (pin "1") (pinfunction "1_1") (pintype "passive"))
      (node (ref "G2") (pin "4") (pinfunction "vcc_4") (pintype "power_in"))
      (node (ref "L5") (pin "2") (pinfunction "2_2") (pintype "passive"))
      (node (ref "P3") (pin "27") (pinfunction "27_27") (pintype "passive"))
      (node (ref "P3") (pin "28") (pinfunction "28_28") (pintype "passive"))
      (node (ref "P3") (pin "29") (pinfunction "29_29") (pintype "passive"))
      (node (ref "P3") (pin "30") (pinfunction "30_30") (pintype "passive"))
      (node (ref "R12") (pin "2") (pinfunction "2_2") (pintype "passive"))
      (node (ref "R14") (pin "2") (pinfunction "2_2") (pintype "passive"))
      (node (ref "R15") (pin "2") (pinfunction "2_2") (pintype "passive"))
      (node (ref "R16") (pin "1") (pinfunction "1_1") (pintype "passive"))
      (node (ref "R17") (pin "1") (pinfunction "1_1") (pintype "passive"))
      (node (ref "R18") (pin "2") (pinfunction "2_2") (pintype "passive"))
      (node (ref "R19") (pin "2") (pinfunction "2_2") (pintype "passive"))
      (node (ref "U4") (pin "B1") (pinfunction "VIO4_B1") (pintype "passive"))
      (node (ref "U4") (pin "C11") (pinfunction "VIO5_C11") (pintype "passive"))
      (node (ref "U4") (pin "E10") (pinfunction "VBAT_E10") (pintype "passive"))
      (node (ref "U4") (pin "E3") (pinfunction "VIO3_E3") (pintype "passive"))
      (node (ref "U4") (pin "F1") (pinfunction "VIO2_F1") (pintype "passive"))
      (node (ref "U4") (pin "H11") (pinfunction "VIO1_2_H11") (pintype "passive"))
      (node (ref "U4") (pin "L9") (pinfunction "VIO1_1_L9") (pintype "passive"))
      (node (ref "U5") (pin "8") (pinfunction "VCC_8") (pintype "passive"))
      (node (ref "U6") (pin "8") (pinfunction "VCC_8") (pintype "passive"))
    )
    (net (code "103") (name "VCC(+5V)") (class "Default")
      (node (ref "C48") (pin "1") (pinfunction "1_1") (pintype "passive"))
      (node (ref "U4") (pin "E11") (pinfunction "VBUS_E11") (pintype "passive"))
    )
    (net (code "104") (name "VDD(+1.2V)") (class "Default")
      (node (ref "C49") (pin "1") (pinfunction "1_1") (pintype "passive"))
      (node (ref "C50") (pin "1") (pinfunction "1_1") (pintype "passive"))
      (node (ref "C51") (pin "1") (pinfunction "1_1") (pintype "passive"))
      (node (ref "C52") (pin "1") (pinfunction "1_1") (pintype "passive"))
      (node (ref "C61") (pin "1") (pinfunction "1_1") (pintype "passive"))
      (node (ref "C62") (pin "1") (pinfunction "1_1") (pintype "passive"))
      (node (ref "C64") (pin "1") (pinfunction "1_1") (pintype "passive"))
      (node (ref "C65") (pin "1") (pinfunction "1_1") (pintype "passive"))
      (node (ref "C78") (pin "2") (pinfunction "2_2") (pintype "passive"))
      (node (ref "L6") (pin "1") (pinfunction "1_1") (pintype "passive"))
      (node (ref "L7") (pin "1") (pinfunction "1_1") (pintype "passive"))
      (node (ref "L8") (pin "1") (pinfunction "1_1") (pintype "passive"))
      (node (ref "U4") (pin "B10") (pinfunction "VDD8_B10") (pintype "passive"))
      (node (ref "U4") (pin "C3") (pinfunction "VDD2_C3") (pintype "passive"))
      (node (ref "U4") (pin "E9") (pinfunction "VDD4_E9") (pintype "passive"))
      (node (ref "U4") (pin "F11") (pinfunction "VDD5_F11") (pintype "passive"))
      (node (ref "U4") (pin "H1") (pinfunction "VDD1_H1") (pintype "passive"))
      (node (ref "U4") (pin "J11") (pinfunction "VDD7_J11") (pintype "passive"))
      (node (ref "U4") (pin "L5") (pinfunction "VDD6_L5") (pintype "passive"))
      (node (ref "U4") (pin "L7") (pinfunction "VDD3_L7") (pintype "passive"))
    )
    (net (code "105") (name "unconnected-(G2-ena-Pad1)") (class "Default")
      (node (ref "G2") (pin "1") (pinfunction "ena_1") (pintype "passive"))
    )
    (net (code "106") (name "unconnected-(RS6-Pad3)") (class "Default")
      (node (ref "RS6") (pin "3") (pinfunction "3_3") (pintype "bidirectional"))
    )
    (net (code "107") (name "unconnected-(RS6-Pad6)") (class "Default")
      (node (ref "RS6") (pin "6") (pinfunction "6_6") (pintype "bidirectional"))
    )
    (net (code "108") (name "unconnected-(U4A-CTL9-PadH6)") (class "Default")
      (node (ref "U4") (pin "H6") (pinfunction "CTL9_H6") (pintype "passive"))
    )
    (net (code "109") (name "unconnected-(U4A-CTL10-PadK5)") (class "Default")
      (node (ref "U4") (pin "K5") (pinfunction "CTL10_K5") (pintype "passive"))
    )
    (net (code "110") (name "unconnected-(U4A-PMODE2-PadL4)") (class "Default")
      (node (ref "U4") (pin "L4") (pinfunction "PMODE2_L4") (pintype "passive+no_connect"))
    )
    (net (code "111") (name "unconnected-(U4B-DQ16-PadK2)") (class "Default")
      (node (ref "U4") (pin "K2") (pinfunction "DQ16_K2") (pintype "passive"))
    )
    (net (code "112") (name "unconnected-(U4B-DQ17-PadJ4)") (class "Default")
      (node (ref "U4") (pin "J4") (pinfunction "DQ17_J4") (pintype "passive"))
    )
    (net (code "113") (name "unconnected-(U4B-DQ18-PadK1)") (class "Default")
      (node (ref "U4") (pin "K1") (pinfunction "DQ18_K1") (pintype "passive"))
    )
    (net (code "114") (name "unconnected-(U4B-DQ19-PadJ2)") (class "Default")
      (node (ref "U4") (pin "J2") (pinfunction "DQ19_J2") (pintype "passive"))
    )
    (net (code "115") (name "unconnected-(U4B-DQ20-PadJ3)") (class "Default")
      (node (ref "U4") (pin "J3") (pinfunction "DQ20_J3") (pintype "passive"))
    )
    (net (code "116") (name "unconnected-(U4B-DQ21-PadJ1)") (class "Default")
      (node (ref "U4") (pin "J1") (pinfunction "DQ21_J1") (pintype "passive"))
    )
    (net (code "117") (name "unconnected-(U4B-DQ22-PadH2)") (class "Default")
      (node (ref "U4") (pin "H2") (pinfunction "DQ22_H2") (pintype "passive"))
    )
    (net (code "118") (name "unconnected-(U4B-DQ23-PadH3)") (class "Default")
      (node (ref "U4") (pin "H3") (pinfunction "DQ23_H3") (pintype "passive"))
    )
    (net (code "119") (name "unconnected-(U4B-DQ24-PadF4)") (class "Default")
      (node (ref "U4") (pin "F4") (pinfunction "DQ24_F4") (pintype "passive"))
    )
    (net (code "120") (name "unconnected-(U4B-DQ25-PadG2)") (class "Default")
      (node (ref "U4") (pin "G2") (pinfunction "DQ25_G2") (pintype "passive"))
    )
    (net (code "121") (name "unconnected-(U4B-DQ26-PadG3)") (class "Default")
      (node (ref "U4") (pin "G3") (pinfunction "DQ26_G3") (pintype "passive"))
    )
    (net (code "122") (name "unconnected-(U4B-DQ27-PadF3)") (class "Default")
      (node (ref "U4") (pin "F3") (pinfunction "DQ27_F3") (pintype "passive"))
    )
    (net (code "123") (name "unconnected-(U4B-GPIO45-PadF2)") (class "Default")
      (node (ref "U4") (pin "F2") (pinfunction "GPIO45_F2") (pintype "passive"))
    )
    (net (code "124") (name "unconnected-(U4C-DQ28-PadF5)") (class "Default")
      (node (ref "U4") (pin "F5") (pinfunction "DQ28_F5") (pintype "passive"))
    )
    (net (code "125") (name "unconnected-(U4C-DQ29-PadE1)") (class "Default")
      (node (ref "U4") (pin "E1") (pinfunction "DQ29_E1") (pintype "passive"))
    )
    (net (code "126") (name "unconnected-(U4C-DQ30-PadE5)") (class "Default")
      (node (ref "U4") (pin "E5") (pinfunction "DQ30_E5") (pintype "passive"))
    )
    (net (code "127") (name "unconnected-(U4C-DQ31-PadE4)") (class "Default")
      (node (ref "U4") (pin "E4") (pinfunction "DQ31_E4") (pintype "passive"))
    )
    (net (code "128") (name "unconnected-(U4C-I2S-CLK-PadD1)") (class "Default")
      (node (ref "U4") (pin "D1") (pinfunction "I2S-CLK_D1") (pintype "passive"))
    )
    (net (code "129") (name "unconnected-(U4C-I2S-MCLK-PadC4)") (class "Default")
      (node (ref "U4") (pin "C4") (pinfunction "I2S-MCLK_C4") (pintype "passive"))
    )
    (net (code "130") (name "unconnected-(U4C-I2S-SD-PadD2)") (class "Default")
      (node (ref "U4") (pin "D2") (pinfunction "I2S-SD_D2") (pintype "passive"))
    )
    (net (code "131") (name "unconnected-(U4C-I2S-WS-PadD3)") (class "Default")
      (node (ref "U4") (pin "D3") (pinfunction "I2S-WS_D3") (pintype "passive"))
    )
    (net (code "132") (name "unconnected-(U4D-NC-PadA11)") (class "Default")
      (node (ref "U4") (pin "A11") (pinfunction "NC_A11") (pintype "passive"))
    )
    (net (code "133") (name "unconnected-(U4E-CLKIN-PadD7)") (class "Default")
      (node (ref "U4") (pin "D7") (pinfunction "CLKIN_D7") (pintype "passive"))
    )
    (net (code "134") (name "unconnected-(U4F-TCK-PadF6)") (class "Default")
      (node (ref "U4") (pin "F6") (pinfunction "TCK_F6") (pintype "passive"))
    )
    (net (code "135") (name "unconnected-(U4F-TDI-PadE7)") (class "Default")
      (node (ref "U4") (pin "E7") (pinfunction "TDI_E7") (pintype "passive"))
    )
    (net (code "136") (name "unconnected-(U4F-TDO-PadC10)") (class "Default")
      (node (ref "U4") (pin "C10") (pinfunction "TDO_C10") (pintype "passive"))
    )
    (net (code "137") (name "unconnected-(U4F-TMS-PadE8)") (class "Default")
      (node (ref "U4") (pin "E8") (pinfunction "TMS_E8") (pintype "passive"))
    )
    (net (code "138") (name "unconnected-(U4F-TRST_N-PadB11)") (class "Default")
      (node (ref "U4") (pin "B11") (pinfunction "TRST_N_B11") (pintype "passive"))
    )
    (net (code "139") (name "unconnected-(U4H-I2C-GPIO60_CHARGER-DETECT-PadD11)") (class "Default")
      (node (ref "U4") (pin "D11") (pinfunction "I2C-GPIO60_CHARGER-DETECT_D11") (pintype "passive+no_connect"))
    )
    (net (code "140") (name "unconnected-(U5-DU1-Pad1)") (class "Default")
      (node (ref "U5") (pin "1") (pinfunction "DU1_1") (pintype "passive"))
    )
    (net (code "141") (name "unconnected-(U5-DU2-Pad2)") (class "Default")
      (node (ref "U5") (pin "2") (pinfunction "DU2_2") (pintype "passive"))
    )
    (net (code "142") (name "unconnected-(U5-E2-Pad3)") (class "Default")
      (node (ref "U5") (pin "3") (pinfunction "E2_3") (pintype "passive"))
    )
    (net (code "143") (name "unconnected-(U5-~{WC}-Pad7)") (class "Default")
      (node (ref "U5") (pin "7") (pinfunction "~{WC}_7") (pintype "passive"))
    )
    (net (code "144") (name "unconnected-(U6-NC-Pad1)") (class "Default")
      (node (ref "U6") (pin "1") (pinfunction "NC_1") (pintype "passive"))
    )
    (net (code "145") (name "unconnected-(U6-NC-Pad2)") (class "Default")
      (node (ref "U6") (pin "2") (pinfunction "NC_2") (pintype "passive"))
    )
    (net (code "146") (name "unconnected-(U6-NC-Pad3)") (class "Default")
      (node (ref "U6") (pin "3") (pinfunction "NC_3") (pintype "passive"))
    )
    (net (code "147") (name "unconnected-(U6-NC-Pad7)") (class "Default")
      (node (ref "U6") (pin "7") (pinfunction "NC_7") (pintype "passive"))
    )
  )
)
